# Power.net
KiCad netlist of a schematic drawn in Altium Designer
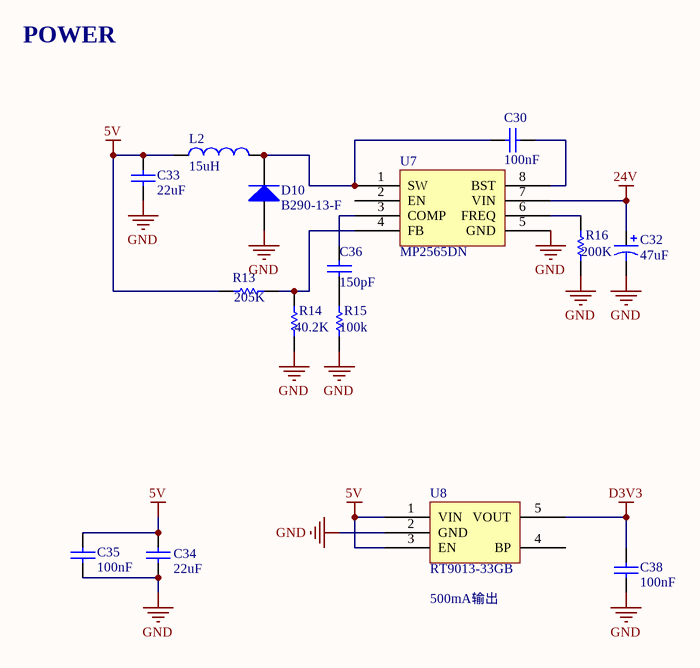
[diagram p0: Power.SchDoc]

(export (version "E")
  (design (tool "Eeschema 10.0.6"))
  (components
    (comp (ref "C30")
      (value "100nF")
      (footprint "BinFeng:0402")
      (description "Capacitor")
      (fields (field (name "PUBLISHER") "Altium Limited"))
      (libsource (lib "Miscellaneous Devices") (part "Cap"))
    )
    (comp (ref "C32")
      (value "47uF")
      (footprint "cap_pol_8*10.2")
      (description "Polarized Capacitor (Radial)")
      (fields (field (name "PUBLISHER") "Altium Limited"))
      (libsource (lib "Miscellaneous Devices") (part "Cap Pol1"))
    )
    (comp (ref "C33")
      (value "22uF")
      (footprint "0805")
      (description "Capacitor,50V")
      (fields (field (name "PUBLISHER") "Altium Limited"))
      (libsource (lib "Miscellaneous Devices") (part "Cap"))
    )
    (comp (ref "C34")
      (value "22uF")
      (footprint "1206")
      (description "Capacitor")
      (fields (field (name "PUBLISHER") "Altium Limited"))
      (libsource (lib "Miscellaneous Devices") (part "Cap"))
    )
    (comp (ref "C35")
      (value "100nF")
      (footprint "BinFeng:0402")
      (description "Capacitor,100V")
      (fields (field (name "PUBLISHER") "Altium Limited"))
      (libsource (lib "Miscellaneous Devices") (part "Cap"))
    )
    (comp (ref "C36")
      (value "150pF")
      (footprint "BinFeng:0402")
      (description "Capacitor")
      (fields (field (name "PUBLISHER") "Altium Limited"))
      (libsource (lib "Miscellaneous Devices") (part "Cap"))
    )
    (comp (ref "C38")
      (value "100nF")
      (footprint "BinFeng:0402")
      (description "Capacitor 3V3")
      (fields (field (name "PUBLISHER") "Altium Limited"))
      (libsource (lib "Miscellaneous Devices") (part "Cap"))
    )
    (comp (ref "D10")
      (value "B290-13-F")
      (footprint "B290")
      (description "Default Diode")
      (fields (field (name "PUBLISHER") "Altium Limited"))
      (libsource (lib "Miscellaneous Devices") (part "Diode"))
    )
    (comp (ref "L2")
      (value "15uH")
      (footprint "10*10Inductor")
      (description "Inductor, 1A")
      (fields (field (name "PUBLISHER") "Altium Limited"))
      (libsource (lib "Miscellaneous Devices") (part "Inductor"))
    )
    (comp (ref "R13")
      (value "205K")
      (footprint "BinFeng:0402")
      (description "Resistor")
      (fields (field (name "PUBLISHER") "Altium Limited"))
      (libsource (lib "Miscellaneous Devices") (part "Res1"))
    )
    (comp (ref "R14")
      (value "40.2K")
      (footprint "BinFeng:0402")
      (description "Resistor")
      (fields (field (name "PUBLISHER") "Altium Limited"))
      (libsource (lib "Miscellaneous Devices") (part "Res1"))
    )
    (comp (ref "R15")
      (value "100k")
      (footprint "BinFeng:0402")
      (description "Resistor")
      (fields (field (name "PUBLISHER") "Altium Limited"))
      (libsource (lib "Miscellaneous Devices") (part "Res1"))
    )
    (comp (ref "R16")
      (value "200K")
      (footprint "BinFeng:0402")
      (description "Resistor")
      (fields (field (name "PUBLISHER") "Altium Limited"))
      (libsource (lib "Miscellaneous Devices") (part "Res1"))
    )
    (comp (ref "U7")
      (value "MP2565DN")
      (footprint "so-8")
      (description "DCDC 4.5V~28V input 1.8V ~5V output low power")
      (libsource (lib "BinFeng_IC") (part "MP1584"))
    )
    (comp (ref "U8")
      (value "RT9013-33GB")
      (footprint "SOT-23-5")
      (libsource (lib "BinFeng_IC") (part "RT9193"))
    )
  )
  (nets
    (net (code "1") (name "5V") (class "Default")
      (node (ref "C33") (pin "2") (pinfunction "2_2") (pintype "passive"))
      (node (ref "C34") (pin "2") (pinfunction "2_2") (pintype "passive"))
      (node (ref "C35") (pin "2") (pinfunction "2_2") (pintype "passive"))
      (node (ref "L2") (pin "1") (pinfunction "1_1") (pintype "passive"))
      (node (ref "R13") (pin "2") (pinfunction "2_2") (pintype "passive"))
      (node (ref "U8") (pin "1") (pinfunction "VIN_1") (pintype "passive"))
      (node (ref "U8") (pin "3") (pinfunction "EN_3") (pintype "passive"))
    )
    (net (code "2") (name "24V") (class "Default")
      (node (ref "C32") (pin "1") (pinfunction "1_1") (pintype "passive"))
      (node (ref "U7") (pin "7") (pinfunction "VIN_7") (pintype "passive"))
    )
    (net (code "3") (name "D3V3") (class "Default")
      (node (ref "C38") (pin "2") (pinfunction "2_2") (pintype "passive"))
      (node (ref "U8") (pin "5") (pinfunction "VOUT_5") (pintype "passive"))
    )
    (net (code "4") (name "GND") (class "Default")
      (node (ref "C32") (pin "2") (pinfunction "2_2") (pintype "passive"))
      (node (ref "C33") (pin "1") (pinfunction "1_1") (pintype "passive"))
      (node (ref "C34") (pin "1") (pinfunction "1_1") (pintype "passive"))
      (node (ref "C35") (pin "1") (pinfunction "1_1") (pintype "passive"))
      (node (ref "C38") (pin "1") (pinfunction "1_1") (pintype "passive"))
      (node (ref "D10") (pin "1") (pinfunction "A_1") (pintype "passive"))
      (node (ref "R14") (pin "1") (pinfunction "1_1") (pintype "passive"))
      (node (ref "R15") (pin "1") (pinfunction "1_1") (pintype "passive"))
      (node (ref "R16") (pin "1") (pinfunction "1_1") (pintype "passive"))
      (node (ref "U7") (pin "5") (pinfunction "GND_5") (pintype "passive"))
      (node (ref "U8") (pin "2") (pinfunction "GND_2") (pintype "passive"))
    )
    (net (code "5") (name "Net-(C36-Pad2)") (class "Default")
      (node (ref "C36") (pin "2") (pinfunction "2_2") (pintype "passive"))
      (node (ref "R15") (pin "2") (pinfunction "2_2") (pintype "passive"))
    )
    (net (code "6") (name "Net-(D10-K)") (class "Default")
      (node (ref "C30") (pin "2") (pinfunction "2_2") (pintype "passive"))
      (node (ref "D10") (pin "2") (pinfunction "K_2") (pintype "passive"))
      (node (ref "L2") (pin "2") (pinfunction "2_2") (pintype "passive"))
      (node (ref "U7") (pin "1") (pinfunction "SW_1") (pintype "passive"))
    )
    (net (code "7") (name "Net-(U7-BST)") (class "Default")
      (node (ref "C30") (pin "1") (pinfunction "1_1") (pintype "passive"))
      (node (ref "U7") (pin "8") (pinfunction "BST_8") (pintype "passive"))
    )
    (net (code "8") (name "Net-(U7-COMP)") (class "Default")
      (node (ref "C36") (pin "1") (pinfunction "1_1") (pintype "passive"))
      (node (ref "U7") (pin "3") (pinfunction "COMP_3") (pintype "passive"))
    )
    (net (code "9") (name "Net-(U7-FB)") (class "Default")
      (node (ref "R13") (pin "1") (pinfunction "1_1") (pintype "passive"))
      (node (ref "R14") (pin "2") (pinfunction "2_2") (pintype "passive"))
      (node (ref "U7") (pin "4") (pinfunction "FB_4") (pintype "passive"))
    )
    (net (code "10") (name "Net-(U7-FREQ)") (class "Default")
      (node (ref "R16") (pin "2") (pinfunction "2_2") (pintype "passive"))
      (node (ref "U7") (pin "6") (pinfunction "FREQ_6") (pintype "passive"))
    )
    (net (code "11") (name "unconnected-(U7-EN-Pad2)") (class "Default")
      (node (ref "U7") (pin "2") (pinfunction "EN_2") (pintype "passive"))
    )
    (net (code "12") (name "unconnected-(U8-BP-Pad4)") (class "Default")
      (node (ref "U8") (pin "4") (pinfunction "BP_4") (pintype "passive"))
    )
  )
)
